# thefly.net
KiCad netlist of a schematic drawn in EAGLE
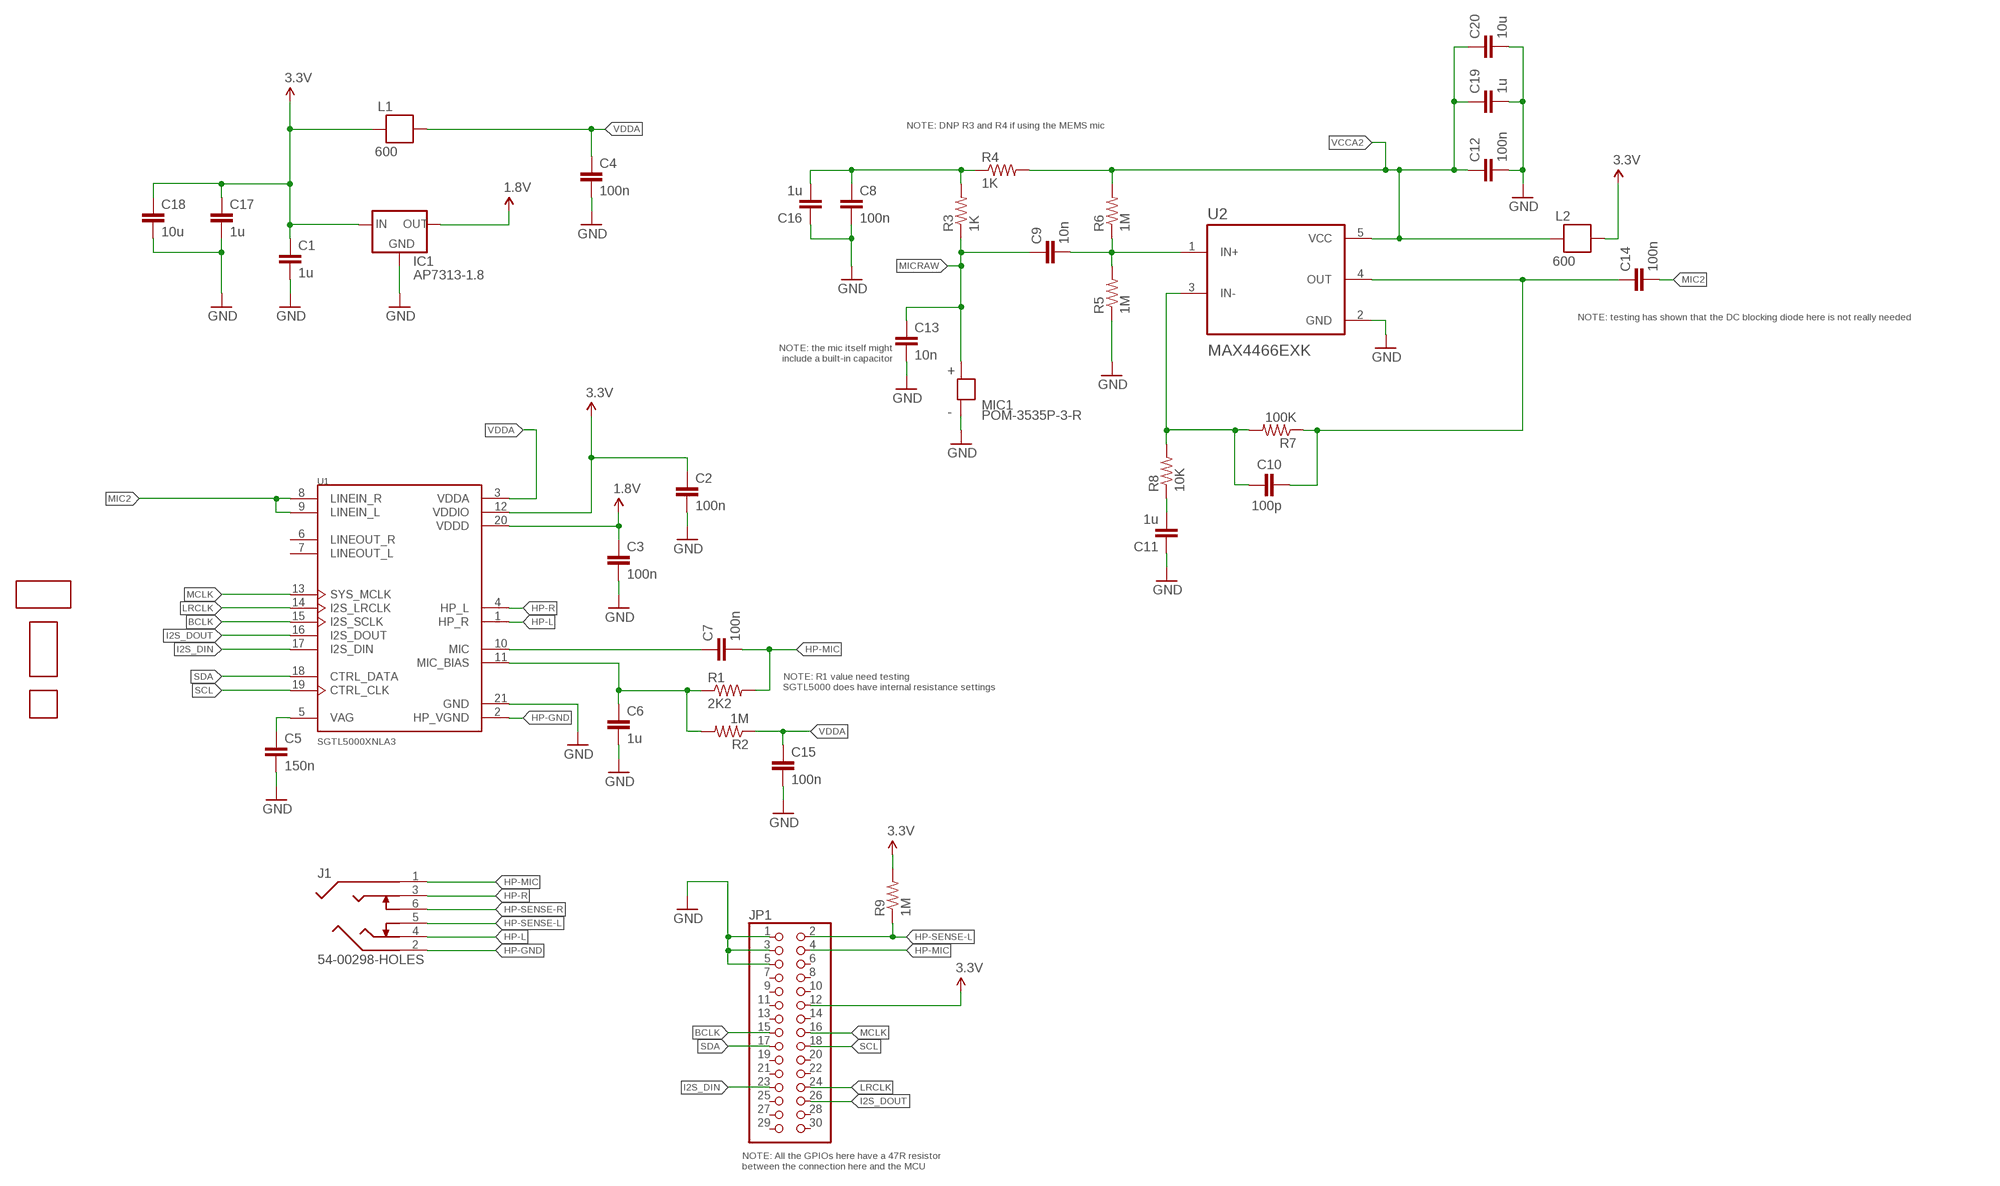
[diagram p0: schematic, sheet 1]

(export (version "E")
  (design (tool "Eeschema 10.0.6"))
  (components
    (comp (ref "C1")
      (value "1u")
      (footprint "eagle-import:0603-CAP")
      (libsource (lib "eagle-import") (part "CAP0603-CAP"))
    )
    (comp (ref "C2")
      (value "100n")
      (footprint "eagle-import:0603-CAP")
      (libsource (lib "eagle-import") (part "CAP0603-CAP"))
    )
    (comp (ref "C3")
      (value "100n")
      (footprint "eagle-import:0603-CAP")
      (libsource (lib "eagle-import") (part "CAP0603-CAP"))
    )
    (comp (ref "C4")
      (value "100n")
      (footprint "eagle-import:0603-CAP")
      (libsource (lib "eagle-import") (part "CAP0603-CAP"))
    )
    (comp (ref "C5")
      (value "150n")
      (footprint "eagle-import:0603-CAP")
      (libsource (lib "eagle-import") (part "CAP0603-CAP"))
    )
    (comp (ref "C6")
      (value "1u")
      (footprint "eagle-import:0603-CAP")
      (libsource (lib "eagle-import") (part "CAP0603-CAP"))
    )
    (comp (ref "C7")
      (value "100n")
      (footprint "eagle-import:0603-CAP")
      (libsource (lib "eagle-import") (part "CAP0603-CAP"))
    )
    (comp (ref "C8")
      (value "100n")
      (footprint "eagle-import:0603-CAP")
      (libsource (lib "eagle-import") (part "CAP0603-CAP"))
    )
    (comp (ref "C9")
      (value "10n")
      (footprint "eagle-import:0603-CAP")
      (libsource (lib "eagle-import") (part "CAP0603-CAP"))
    )
    (comp (ref "C10")
      (value "100p")
      (footprint "eagle-import:0603-CAP")
      (libsource (lib "eagle-import") (part "CAP0603-CAP"))
    )
    (comp (ref "C11")
      (value "1u")
      (footprint "eagle-import:0603-CAP")
      (libsource (lib "eagle-import") (part "CAP0603-CAP"))
    )
    (comp (ref "C12")
      (value "100n")
      (footprint "eagle-import:0603-CAP")
      (libsource (lib "eagle-import") (part "CAP0603-CAP"))
    )
    (comp (ref "C13")
      (value "10n")
      (footprint "eagle-import:0603-CAP")
      (libsource (lib "eagle-import") (part "CAP0603-CAP"))
    )
    (comp (ref "C14")
      (value "100n")
      (footprint "eagle-import:0603-CAP")
      (libsource (lib "eagle-import") (part "CAP0603-CAP"))
    )
    (comp (ref "C15")
      (value "100n")
      (footprint "eagle-import:0603-CAP")
      (libsource (lib "eagle-import") (part "CAP0603-CAP"))
    )
    (comp (ref "C16")
      (value "1u")
      (footprint "eagle-import:0603-CAP")
      (libsource (lib "eagle-import") (part "CAP0603-CAP"))
    )
    (comp (ref "C17")
      (value "1u")
      (footprint "eagle-import:0603-CAP")
      (libsource (lib "eagle-import") (part "CAP0603-CAP"))
    )
    (comp (ref "C18")
      (value "10u")
      (footprint "eagle-import:0603-CAP")
      (libsource (lib "eagle-import") (part "CAP0603-CAP"))
    )
    (comp (ref "C19")
      (value "1u")
      (footprint "eagle-import:0603-CAP")
      (libsource (lib "eagle-import") (part "CAP0603-CAP"))
    )
    (comp (ref "C20")
      (value "10u")
      (footprint "eagle-import:0603-CAP")
      (libsource (lib "eagle-import") (part "CAP0603-CAP"))
    )
    (comp (ref "IC1")
      (value "AP7313-1.8")
      (footprint "eagle-import:SOT23-3")
      (libsource (lib "eagle-import") (part "V_REG_78XX-SOT23-3"))
    )
    (comp (ref "J1")
      (value "54-00298-HOLES")
      (footprint "eagle-import:TENSILITY_54-00298_HOLES")
      (libsource (lib "eagle-import") (part "54-00298-HOLES"))
    )
    (comp (ref "JP1")
      (value "PINHD-2X15-SMD-R")
      (footprint "eagle-import:2X15-SMD-R")
      (libsource (lib "eagle-import") (part "PINHD-2X15-SMD-R"))
    )
    (comp (ref "L1")
      (value "600")
      (footprint "eagle-import:0603")
      (libsource (lib "eagle-import") (part "FB"))
    )
    (comp (ref "L2")
      (value "600")
      (footprint "eagle-import:0603")
      (libsource (lib "eagle-import") (part "FB"))
    )
    (comp (ref "MIC1")
      (value "POM-3535P-3-R")
      (footprint "eagle-import:MIC_POM-3535P-3-R")
      (fields (field (name "DIGIKEY_PART_NUMBER") "668-1425-ND") (field (name "MF") "PUI Audio"))
      (libsource (lib "eagle-import") (part "POM-3535P-3-R"))
    )
    (comp (ref "R1")
      (value "2K2")
      (footprint "eagle-import:0603-RES")
      (libsource (lib "eagle-import") (part "RESISTOR0603-RES"))
    )
    (comp (ref "R2")
      (value "1M")
      (footprint "eagle-import:0603-RES")
      (libsource (lib "eagle-import") (part "RESISTOR0603-RES"))
    )
    (comp (ref "R3")
      (value "1K")
      (footprint "eagle-import:0603-RES")
      (libsource (lib "eagle-import") (part "RESISTOR0603-RES"))
    )
    (comp (ref "R4")
      (value "1K")
      (footprint "eagle-import:0603-RES")
      (libsource (lib "eagle-import") (part "RESISTOR0603-RES"))
    )
    (comp (ref "R5")
      (value "1M")
      (footprint "eagle-import:0603-RES")
      (libsource (lib "eagle-import") (part "RESISTOR0603-RES"))
    )
    (comp (ref "R6")
      (value "1M")
      (footprint "eagle-import:0603-RES")
      (libsource (lib "eagle-import") (part "RESISTOR0603-RES"))
    )
    (comp (ref "R7")
      (value "100K")
      (footprint "eagle-import:0603-RES")
      (libsource (lib "eagle-import") (part "RESISTOR0603-RES"))
    )
    (comp (ref "R8")
      (value "10K")
      (footprint "eagle-import:0603-RES")
      (libsource (lib "eagle-import") (part "RESISTOR0603-RES"))
    )
    (comp (ref "R9")
      (value "1M")
      (footprint "eagle-import:0603-RES")
      (libsource (lib "eagle-import") (part "RESISTOR0603-RES"))
    )
    (comp (ref "U$1")
      (value "M5STACK-CORE2-DAUGHTER")
      (footprint "eagle-import:M5STACK-CORE2-DAUGHTER")
      (libsource (lib "eagle-import") (part "M5STACK-CORE2-DAUGHTER"))
    )
    (comp (ref "U$2")
      (value "M5STACK-BATT-OUTLINE")
      (footprint "eagle-import:M5STACK-BATT-OUTLINE")
      (libsource (lib "eagle-import") (part "M5STACK-BATT-OUTLINE"))
    )
    (comp (ref "U$5")
      (value "THE-FLY-LOGO")
      (footprint "eagle-import:THE-FLY-LOGO")
      (libsource (lib "eagle-import") (part "THE-FLY-LOGO"))
    )
    (comp (ref "U1")
      (value "SGTL5000XNLA3")
      (footprint "eagle-import:QFN40P300X300X60-21N")
      (fields (field (name "MF") "NXP Semiconductors"))
      (libsource (lib "eagle-import") (part "SGTL5000XNLA3"))
    )
    (comp (ref "U2")
      (value "MAX4466EXK")
      (footprint "eagle-import:SOT65P210X110-5N")
      (fields
        (field (name "DIGIKEY_PART_NUMBER") "MAX4466EXK+CT-ND")
        (field (name "MF") "Maxim Integrated Products")
        (field (name "MP") "MAX4466EXK+T")
      )
      (libsource (lib "eagle-import") (part "MAX4466EXK"))
    )
  )
  (nets
    (net (code "1") (name "1.8V") (class "Default")
      (node (ref "C3") (pin "1") (pinfunction "1_1") (pintype "passive"))
      (node (ref "IC1") (pin "2") (pinfunction "OUT_2") (pintype "output"))
      (node (ref "U1") (pin "20") (pinfunction "VDDD_20") (pintype "power_in"))
    )
    (net (code "2") (name "3.3V") (class "Default")
      (node (ref "C1") (pin "1") (pinfunction "1_1") (pintype "passive"))
      (node (ref "C17") (pin "1") (pinfunction "1_1") (pintype "passive"))
      (node (ref "C18") (pin "1") (pinfunction "1_1") (pintype "passive"))
      (node (ref "C2") (pin "1") (pinfunction "1_1") (pintype "passive"))
      (node (ref "IC1") (pin "1") (pinfunction "IN_1") (pintype "input"))
      (node (ref "JP1") (pin "12") (pinfunction "12_12") (pintype "passive"))
      (node (ref "L1") (pin "2") (pinfunction "P$2_2") (pintype "bidirectional"))
      (node (ref "L2") (pin "1") (pinfunction "P$1_1") (pintype "bidirectional"))
      (node (ref "R9") (pin "2") (pinfunction "2_2") (pintype "passive"))
      (node (ref "U1") (pin "12") (pinfunction "VDDIO_12") (pintype "power_in"))
    )
    (net (code "3") (name "BCLK") (class "Default")
      (node (ref "JP1") (pin "15") (pinfunction "15_15") (pintype "passive"))
      (node (ref "U1") (pin "15") (pinfunction "I2S_SCLK_15") (pintype "bidirectional"))
    )
    (net (code "4") (name "GND") (class "Default")
      (node (ref "C1") (pin "2") (pinfunction "2_2") (pintype "passive"))
      (node (ref "C11") (pin "1") (pinfunction "1_1") (pintype "passive"))
      (node (ref "C12") (pin "2") (pinfunction "2_2") (pintype "passive"))
      (node (ref "C13") (pin "2") (pinfunction "2_2") (pintype "passive"))
      (node (ref "C15") (pin "2") (pinfunction "2_2") (pintype "passive"))
      (node (ref "C16") (pin "1") (pinfunction "1_1") (pintype "passive"))
      (node (ref "C17") (pin "2") (pinfunction "2_2") (pintype "passive"))
      (node (ref "C18") (pin "2") (pinfunction "2_2") (pintype "passive"))
      (node (ref "C19") (pin "2") (pinfunction "2_2") (pintype "passive"))
      (node (ref "C2") (pin "2") (pinfunction "2_2") (pintype "passive"))
      (node (ref "C20") (pin "2") (pinfunction "2_2") (pintype "passive"))
      (node (ref "C3") (pin "2") (pinfunction "2_2") (pintype "passive"))
      (node (ref "C4") (pin "2") (pinfunction "2_2") (pintype "passive"))
      (node (ref "C5") (pin "2") (pinfunction "2_2") (pintype "passive"))
      (node (ref "C6") (pin "2") (pinfunction "2_2") (pintype "passive"))
      (node (ref "C8") (pin "2") (pinfunction "2_2") (pintype "passive"))
      (node (ref "IC1") (pin "3") (pinfunction "GND_3") (pintype "input"))
      (node (ref "JP1") (pin "1") (pinfunction "1_1") (pintype "passive"))
      (node (ref "JP1") (pin "3") (pinfunction "3_3") (pintype "passive"))
      (node (ref "JP1") (pin "5") (pinfunction "5_5") (pintype "passive"))
      (node (ref "MIC1") (pin "N") (pinfunction "-_N") (pintype "passive"))
      (node (ref "R5") (pin "1") (pinfunction "1_1") (pintype "passive"))
      (node (ref "U1") (pin "21") (pinfunction "GND_21") (pintype "power_in"))
      (node (ref "U2") (pin "2") (pinfunction "GND_2") (pintype "power_in"))
    )
    (net (code "5") (name "HP-GND") (class "Default")
      (node (ref "J1") (pin "2") (pinfunction "2_2") (pintype "passive"))
      (node (ref "U1") (pin "2") (pinfunction "HP_VGND_2") (pintype "power_in"))
    )
    (net (code "6") (name "HP-L") (class "Default")
      (node (ref "J1") (pin "4") (pinfunction "4_4") (pintype "passive"))
      (node (ref "U1") (pin "1") (pinfunction "HP_R_1") (pintype "output"))
    )
    (net (code "7") (name "HP-MIC") (class "Default")
      (node (ref "C7") (pin "2") (pinfunction "2_2") (pintype "passive"))
      (node (ref "J1") (pin "1") (pinfunction "1_1") (pintype "passive"))
      (node (ref "JP1") (pin "4") (pinfunction "4_4") (pintype "passive"))
      (node (ref "R1") (pin "2") (pinfunction "2_2") (pintype "passive"))
    )
    (net (code "8") (name "HP-R") (class "Default")
      (node (ref "J1") (pin "3") (pinfunction "3_3") (pintype "passive"))
      (node (ref "U1") (pin "4") (pinfunction "HP_L_4") (pintype "output"))
    )
    (net (code "9") (name "HP-SENSE-L") (class "Default")
      (node (ref "J1") (pin "5") (pinfunction "5_5") (pintype "passive"))
      (node (ref "JP1") (pin "2") (pinfunction "2_2") (pintype "passive"))
      (node (ref "R9") (pin "1") (pinfunction "1_1") (pintype "passive"))
    )
    (net (code "10") (name "HP-SENSE-R") (class "Default")
      (node (ref "J1") (pin "6") (pinfunction "6_6") (pintype "passive"))
    )
    (net (code "11") (name "I2S_DIN") (class "Default")
      (node (ref "JP1") (pin "23") (pinfunction "23_23") (pintype "passive"))
      (node (ref "U1") (pin "17") (pinfunction "I2S_DIN_17") (pintype "bidirectional"))
    )
    (net (code "12") (name "I2S_DOUT") (class "Default")
      (node (ref "JP1") (pin "26") (pinfunction "26_26") (pintype "passive"))
      (node (ref "U1") (pin "16") (pinfunction "I2S_DOUT_16") (pintype "output"))
    )
    (net (code "13") (name "LRCLK") (class "Default")
      (node (ref "JP1") (pin "24") (pinfunction "24_24") (pintype "passive"))
      (node (ref "U1") (pin "14") (pinfunction "I2S_LRCLK_14") (pintype "bidirectional"))
    )
    (net (code "14") (name "MCLK") (class "Default")
      (node (ref "JP1") (pin "16") (pinfunction "16_16") (pintype "passive"))
      (node (ref "U1") (pin "13") (pinfunction "SYS_MCLK_13") (pintype "bidirectional"))
    )
    (net (code "15") (name "MIC2") (class "Default")
      (node (ref "C14") (pin "2") (pinfunction "2_2") (pintype "passive"))
      (node (ref "U1") (pin "8") (pinfunction "LINEIN_R_8") (pintype "input"))
      (node (ref "U1") (pin "9") (pinfunction "LINEIN_L_9") (pintype "input"))
    )
    (net (code "16") (name "MICRAW") (class "Default")
      (node (ref "C13") (pin "1") (pinfunction "1_1") (pintype "passive"))
      (node (ref "C9") (pin "1") (pinfunction "1_1") (pintype "passive"))
      (node (ref "MIC1") (pin "P") (pinfunction "+_P") (pintype "passive"))
      (node (ref "R3") (pin "1") (pinfunction "1_1") (pintype "passive"))
    )
    (net (code "17") (name "Net-(C11-Pad2)") (class "Default")
      (node (ref "C11") (pin "2") (pinfunction "2_2") (pintype "passive"))
      (node (ref "R8") (pin "1") (pinfunction "1_1") (pintype "passive"))
    )
    (net (code "18") (name "Net-(C16-Pad2)") (class "Default")
      (node (ref "C16") (pin "2") (pinfunction "2_2") (pintype "passive"))
      (node (ref "C8") (pin "1") (pinfunction "1_1") (pintype "passive"))
      (node (ref "R3") (pin "2") (pinfunction "2_2") (pintype "passive"))
      (node (ref "R4") (pin "1") (pinfunction "1_1") (pintype "passive"))
    )
    (net (code "19") (name "Net-(U1-MIC)") (class "Default")
      (node (ref "C7") (pin "1") (pinfunction "1_1") (pintype "passive"))
      (node (ref "U1") (pin "10") (pinfunction "MIC_10") (pintype "input"))
    )
    (net (code "20") (name "Net-(U1-MIC_BIAS)") (class "Default")
      (node (ref "C6") (pin "1") (pinfunction "1_1") (pintype "passive"))
      (node (ref "R1") (pin "1") (pinfunction "1_1") (pintype "passive"))
      (node (ref "R2") (pin "2") (pinfunction "2_2") (pintype "passive"))
      (node (ref "U1") (pin "11") (pinfunction "MIC_BIAS_11") (pintype "bidirectional"))
    )
    (net (code "21") (name "Net-(U1-VAG)") (class "Default")
      (node (ref "C5") (pin "1") (pinfunction "1_1") (pintype "passive"))
      (node (ref "U1") (pin "5") (pinfunction "VAG_5") (pintype "bidirectional"))
    )
    (net (code "22") (name "Net-(U2-IN+)") (class "Default")
      (node (ref "C9") (pin "2") (pinfunction "2_2") (pintype "passive"))
      (node (ref "R5") (pin "2") (pinfunction "2_2") (pintype "passive"))
      (node (ref "R6") (pin "1") (pinfunction "1_1") (pintype "passive"))
      (node (ref "U2") (pin "1") (pinfunction "IN+_1") (pintype "input"))
    )
    (net (code "23") (name "Net-(U2-IN-)") (class "Default")
      (node (ref "C10") (pin "1") (pinfunction "1_1") (pintype "passive"))
      (node (ref "R7") (pin "2") (pinfunction "2_2") (pintype "passive"))
      (node (ref "R8") (pin "2") (pinfunction "2_2") (pintype "passive"))
      (node (ref "U2") (pin "3") (pinfunction "IN-_3") (pintype "input"))
    )
    (net (code "24") (name "Net-(U2-OUT)") (class "Default")
      (node (ref "C10") (pin "2") (pinfunction "2_2") (pintype "passive"))
      (node (ref "C14") (pin "1") (pinfunction "1_1") (pintype "passive"))
      (node (ref "R7") (pin "1") (pinfunction "1_1") (pintype "passive"))
      (node (ref "U2") (pin "4") (pinfunction "OUT_4") (pintype "output"))
    )
    (net (code "25") (name "SCL") (class "Default")
      (node (ref "JP1") (pin "18") (pinfunction "18_18") (pintype "passive"))
      (node (ref "U1") (pin "19") (pinfunction "CTRL_CLK_19") (pintype "bidirectional"))
    )
    (net (code "26") (name "SDA") (class "Default")
      (node (ref "JP1") (pin "17") (pinfunction "17_17") (pintype "passive"))
      (node (ref "U1") (pin "18") (pinfunction "CTRL_DATA_18") (pintype "bidirectional"))
    )
    (net (code "27") (name "VCCA2") (class "Default")
      (node (ref "C12") (pin "1") (pinfunction "1_1") (pintype "passive"))
      (node (ref "C19") (pin "1") (pinfunction "1_1") (pintype "passive"))
      (node (ref "C20") (pin "1") (pinfunction "1_1") (pintype "passive"))
      (node (ref "L2") (pin "2") (pinfunction "P$2_2") (pintype "bidirectional"))
      (node (ref "R4") (pin "2") (pinfunction "2_2") (pintype "passive"))
      (node (ref "R6") (pin "2") (pinfunction "2_2") (pintype "passive"))
      (node (ref "U2") (pin "5") (pinfunction "VCC_5") (pintype "power_in"))
    )
    (net (code "28") (name "VDDA") (class "Default")
      (node (ref "C15") (pin "1") (pinfunction "1_1") (pintype "passive"))
      (node (ref "C4") (pin "1") (pinfunction "1_1") (pintype "passive"))
      (node (ref "L1") (pin "1") (pinfunction "P$1_1") (pintype "bidirectional"))
      (node (ref "R2") (pin "1") (pinfunction "1_1") (pintype "passive"))
      (node (ref "U1") (pin "3") (pinfunction "VDDA_3") (pintype "power_in"))
    )
    (net (code "29") (name "unconnected-(JP1-Pad6)") (class "Default")
      (node (ref "JP1") (pin "6") (pinfunction "6_6") (pintype "passive"))
    )
    (net (code "30") (name "unconnected-(JP1-Pad7)") (class "Default")
      (node (ref "JP1") (pin "7") (pinfunction "7_7") (pintype "passive"))
    )
    (net (code "31") (name "unconnected-(JP1-Pad8)") (class "Default")
      (node (ref "JP1") (pin "8") (pinfunction "8_8") (pintype "passive"))
    )
    (net (code "32") (name "unconnected-(JP1-Pad9)") (class "Default")
      (node (ref "JP1") (pin "9") (pinfunction "9_9") (pintype "passive"))
    )
    (net (code "33") (name "unconnected-(JP1-Pad10)") (class "Default")
      (node (ref "JP1") (pin "10") (pinfunction "10_10") (pintype "passive"))
    )
    (net (code "34") (name "unconnected-(JP1-Pad11)") (class "Default")
      (node (ref "JP1") (pin "11") (pinfunction "11_11") (pintype "passive"))
    )
    (net (code "35") (name "unconnected-(JP1-Pad13)") (class "Default")
      (node (ref "JP1") (pin "13") (pinfunction "13_13") (pintype "passive"))
    )
    (net (code "36") (name "unconnected-(JP1-Pad14)") (class "Default")
      (node (ref "JP1") (pin "14") (pinfunction "14_14") (pintype "passive"))
    )
    (net (code "37") (name "unconnected-(JP1-Pad19)") (class "Default")
      (node (ref "JP1") (pin "19") (pinfunction "19_19") (pintype "passive"))
    )
    (net (code "38") (name "unconnected-(JP1-Pad20)") (class "Default")
      (node (ref "JP1") (pin "20") (pinfunction "20_20") (pintype "passive"))
    )
    (net (code "39") (name "unconnected-(JP1-Pad21)") (class "Default")
      (node (ref "JP1") (pin "21") (pinfunction "21_21") (pintype "passive"))
    )
    (net (code "40") (name "unconnected-(JP1-Pad22)") (class "Default")
      (node (ref "JP1") (pin "22") (pinfunction "22_22") (pintype "passive"))
    )
    (net (code "41") (name "unconnected-(JP1-Pad25)") (class "Default")
      (node (ref "JP1") (pin "25") (pinfunction "25_25") (pintype "passive"))
    )
    (net (code "42") (name "unconnected-(JP1-Pad27)") (class "Default")
      (node (ref "JP1") (pin "27") (pinfunction "27_27") (pintype "passive"))
    )
    (net (code "43") (name "unconnected-(JP1-Pad28)") (class "Default")
      (node (ref "JP1") (pin "28") (pinfunction "28_28") (pintype "passive"))
    )
    (net (code "44") (name "unconnected-(JP1-Pad29)") (class "Default")
      (node (ref "JP1") (pin "29") (pinfunction "29_29") (pintype "passive"))
    )
    (net (code "45") (name "unconnected-(JP1-Pad30)") (class "Default")
      (node (ref "JP1") (pin "30") (pinfunction "30_30") (pintype "passive"))
    )
    (net (code "46") (name "unconnected-(U1-LINEOUT_L-Pad7)") (class "Default")
      (node (ref "U1") (pin "7") (pinfunction "LINEOUT_L_7") (pintype "output"))
    )
    (net (code "47") (name "unconnected-(U1-LINEOUT_R-Pad6)") (class "Default")
      (node (ref "U1") (pin "6") (pinfunction "LINEOUT_R_6") (pintype "output"))
    )
  )
)
